# cnc_driver_3.net
KiCad netlist of a schematic drawn in EAGLE
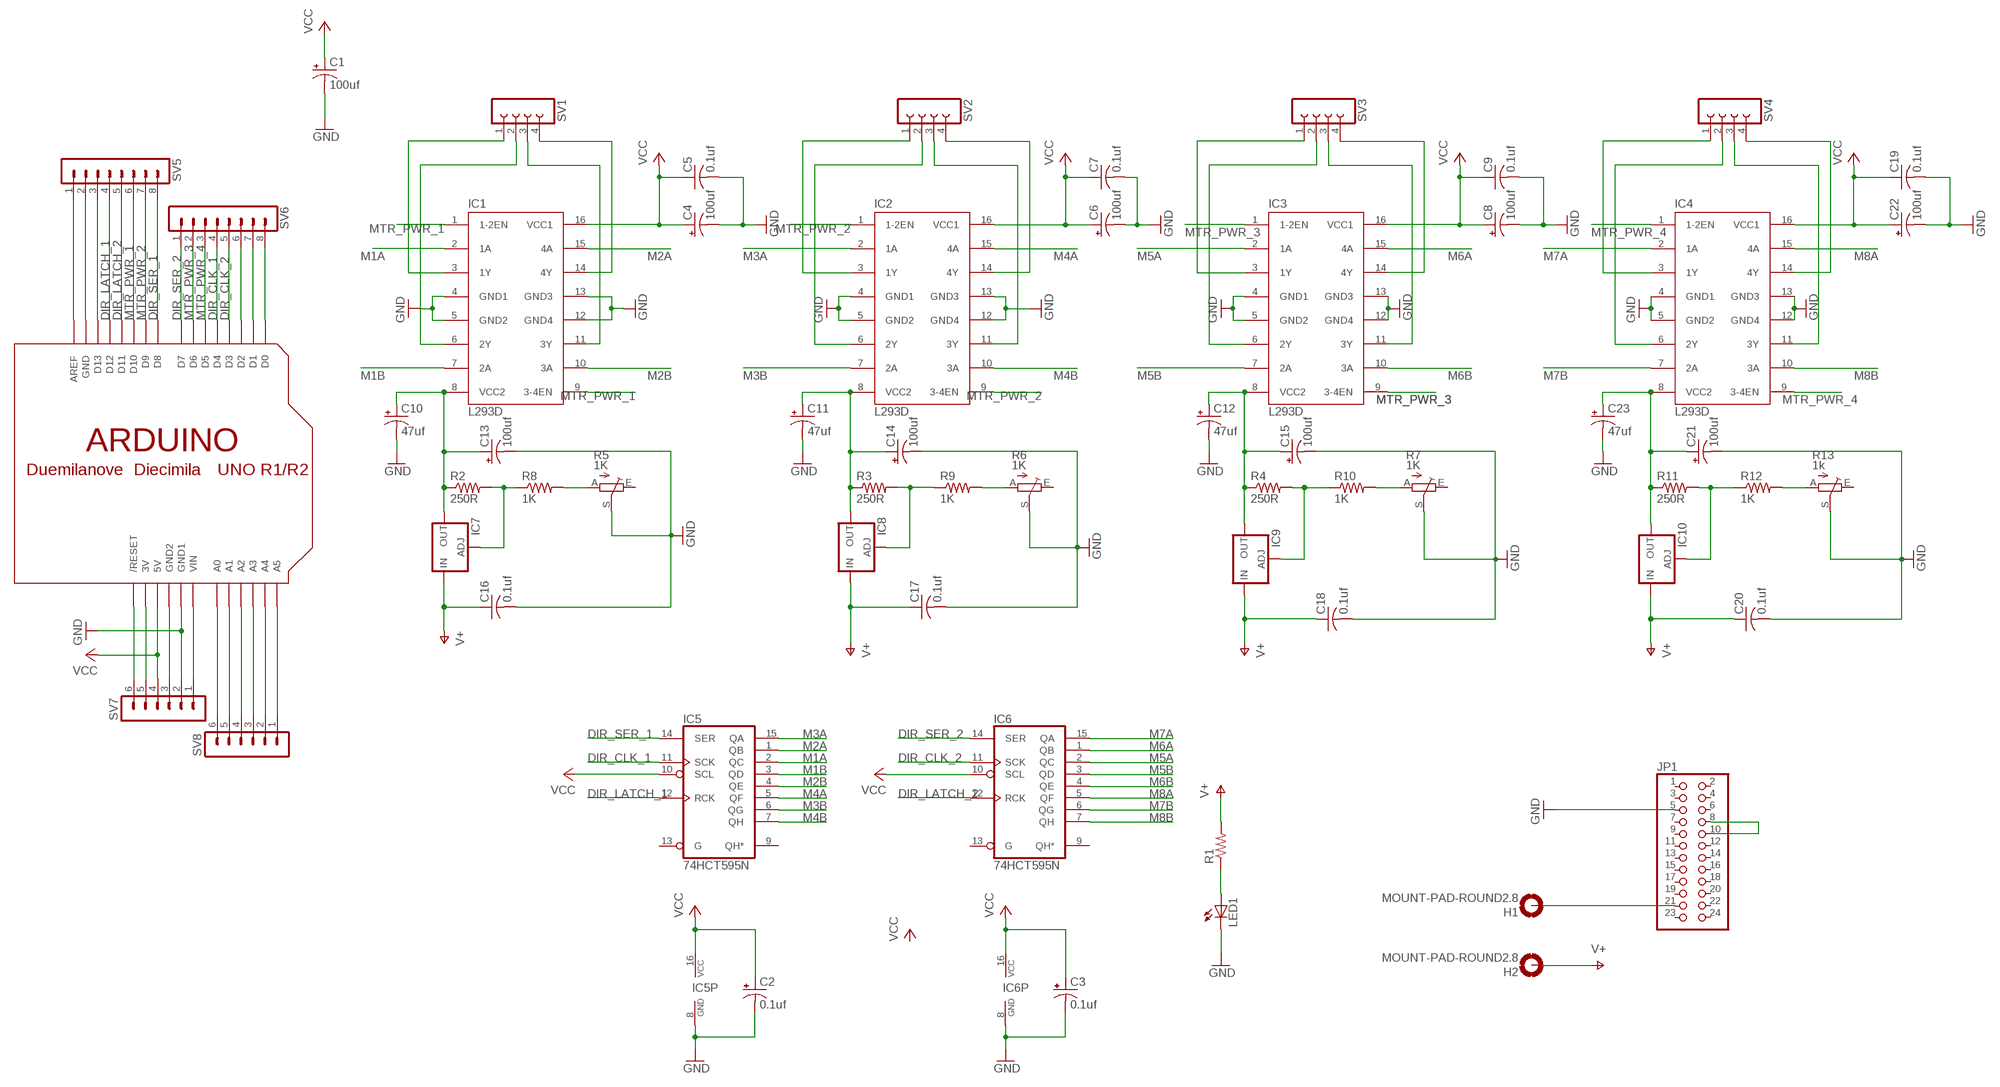
[diagram p0: schematic, sheet 1]

(export (version "E")
  (design (tool "Eeschema 10.0.6"))
  (components
    (comp (ref "C1")
      (value "100uf")
      (footprint "eagle-import:E2-5")
      (libsource (lib "eagle-import") (part "CPOL-USE2-5"))
    )
    (comp (ref "C2")
      (value "0.1uf")
      (footprint "eagle-import:E2-5")
      (libsource (lib "eagle-import") (part "CPOL-USE2-5"))
    )
    (comp (ref "C3")
      (value "0.1uf")
      (footprint "eagle-import:E2-5")
      (libsource (lib "eagle-import") (part "CPOL-USE2-5"))
    )
    (comp (ref "C4")
      (value "100uf")
      (footprint "eagle-import:E2-5")
      (libsource (lib "eagle-import") (part "CPOL-USE2-5"))
    )
    (comp (ref "C5")
      (value "0.1uf")
      (footprint "eagle-import:C025-025X050")
      (libsource (lib "eagle-import") (part "C-US025-025X050"))
    )
    (comp (ref "C6")
      (value "100uf")
      (footprint "eagle-import:E2-5")
      (libsource (lib "eagle-import") (part "CPOL-USE2-5"))
    )
    (comp (ref "C7")
      (value "0.1uf")
      (footprint "eagle-import:C025-025X050")
      (libsource (lib "eagle-import") (part "C-US025-025X050"))
    )
    (comp (ref "C8")
      (value "100uf")
      (footprint "eagle-import:E2-5")
      (libsource (lib "eagle-import") (part "CPOL-USE2-5"))
    )
    (comp (ref "C9")
      (value "0.1uf")
      (footprint "eagle-import:C025-025X050")
      (libsource (lib "eagle-import") (part "C-US025-025X050"))
    )
    (comp (ref "C10")
      (value "47uf")
      (footprint "eagle-import:E2-5")
      (libsource (lib "eagle-import") (part "CPOL-USE2-5"))
    )
    (comp (ref "C11")
      (value "47uf")
      (footprint "eagle-import:E2-5")
      (libsource (lib "eagle-import") (part "CPOL-USE2-5"))
    )
    (comp (ref "C12")
      (value "47uf")
      (footprint "eagle-import:E2-5")
      (libsource (lib "eagle-import") (part "CPOL-USE2-5"))
    )
    (comp (ref "C13")
      (value "100uf")
      (footprint "eagle-import:E3,5-8")
      (libsource (lib "eagle-import") (part "CPOL-USE3.5-8"))
    )
    (comp (ref "C14")
      (value "100uf")
      (footprint "eagle-import:E3,5-8")
      (libsource (lib "eagle-import") (part "CPOL-USE3.5-8"))
    )
    (comp (ref "C15")
      (value "100uf")
      (footprint "eagle-import:E3,5-8")
      (libsource (lib "eagle-import") (part "CPOL-USE3.5-8"))
    )
    (comp (ref "C16")
      (value "0.1uf")
      (footprint "eagle-import:C025-024X044")
      (libsource (lib "eagle-import") (part "C-US025-024X044"))
    )
    (comp (ref "C17")
      (value "0.1uf")
      (footprint "eagle-import:C025-024X044")
      (libsource (lib "eagle-import") (part "C-US025-024X044"))
    )
    (comp (ref "C18")
      (value "0.1uf")
      (footprint "eagle-import:C025-024X044")
      (libsource (lib "eagle-import") (part "C-US025-024X044"))
    )
    (comp (ref "C19")
      (value "0.1uf")
      (footprint "eagle-import:C025-025X050")
      (libsource (lib "eagle-import") (part "C-US025-025X050"))
    )
    (comp (ref "C20")
      (value "0.1uf")
      (footprint "eagle-import:C025-025X050")
      (libsource (lib "eagle-import") (part "C-US025-025X050"))
    )
    (comp (ref "C21")
      (value "100uf")
      (footprint "eagle-import:E3,5-8")
      (libsource (lib "eagle-import") (part "CPOL-USE3.5-8"))
    )
    (comp (ref "C22")
      (value "100uf")
      (footprint "eagle-import:E3,5-8")
      (libsource (lib "eagle-import") (part "CPOL-USE3.5-8"))
    )
    (comp (ref "C23")
      (value "47uf")
      (footprint "eagle-import:E3,5-8")
      (libsource (lib "eagle-import") (part "CPOL-USE3.5-8"))
    )
    (comp (ref "H1")
      (value "MOUNT-PAD-ROUND2.8")
      (footprint "eagle-import:2,8-PAD")
      (libsource (lib "eagle-import") (part "MOUNT-PAD-ROUND2.8"))
    )
    (comp (ref "H2")
      (value "MOUNT-PAD-ROUND2.8")
      (footprint "eagle-import:2,8-PAD")
      (libsource (lib "eagle-import") (part "MOUNT-PAD-ROUND2.8"))
    )
    (comp (ref "IC1")
      (value "L293D")
      (footprint "eagle-import:DIL16")
      (libsource (lib "eagle-import") (part "L293D"))
    )
    (comp (ref "IC2")
      (value "L293D")
      (footprint "eagle-import:DIL16")
      (libsource (lib "eagle-import") (part "L293D"))
    )
    (comp (ref "IC3")
      (value "L293D")
      (footprint "eagle-import:DIL16")
      (libsource (lib "eagle-import") (part "L293D"))
    )
    (comp (ref "IC4")
      (value "L293D")
      (footprint "eagle-import:DIL16")
      (libsource (lib "eagle-import") (part "L293D"))
    )
    (comp (ref "IC5")
      (value "74HCT595N")
      (footprint "eagle-import:DIL16")
      (libsource (lib "eagle-import") (part "74595NHCT"))
    )
    (comp (ref "IC6")
      (value "74HCT595N")
      (footprint "eagle-import:DIL16")
      (libsource (lib "eagle-import") (part "74595NHCT"))
    )
    (comp (ref "IC7")
      (value "LM317TS")
      (footprint "eagle-import:317TS")
      (libsource (lib "eagle-import") (part "LM317TS"))
    )
    (comp (ref "IC8")
      (value "LM317TS")
      (footprint "eagle-import:317TS")
      (libsource (lib "eagle-import") (part "LM317TS"))
    )
    (comp (ref "IC9")
      (value "LM317TS")
      (footprint "eagle-import:317TS")
      (libsource (lib "eagle-import") (part "LM317TS"))
    )
    (comp (ref "IC10")
      (value "LM317TS")
      (footprint "eagle-import:317TS")
      (libsource (lib "eagle-import") (part "LM317TS"))
    )
    (comp (ref "JP1")
      (value "PINHD-2X12")
      (footprint "eagle-import:2X12")
      (libsource (lib "eagle-import") (part "PINHD-2X12"))
    )
    (comp (ref "LED1")
      (value "LED5MM")
      (footprint "eagle-import:LED5MM")
      (libsource (lib "eagle-import") (part "LED5MM"))
    )
    (comp (ref "R1")
      (value "R-US_0204/7")
      (footprint "eagle-import:0204_7")
      (libsource (lib "eagle-import") (part "R-US_0204/7"))
    )
    (comp (ref "R2")
      (value "250R")
      (footprint "eagle-import:0207_7")
      (libsource (lib "eagle-import") (part "R-US_0207/7"))
    )
    (comp (ref "R3")
      (value "250R")
      (footprint "eagle-import:0207_7")
      (libsource (lib "eagle-import") (part "R-US_0207/7"))
    )
    (comp (ref "R4")
      (value "250R")
      (footprint "eagle-import:0207_7")
      (libsource (lib "eagle-import") (part "R-US_0207/7"))
    )
    (comp (ref "R5")
      (value "1K")
      (footprint "eagle-import:CA9H")
      (libsource (lib "eagle-import") (part "TRIM_EU-CA9H"))
    )
    (comp (ref "R6")
      (value "1K")
      (footprint "eagle-import:CA9H")
      (libsource (lib "eagle-import") (part "TRIM_EU-CA9H"))
    )
    (comp (ref "R7")
      (value "1K")
      (footprint "eagle-import:CA9H")
      (libsource (lib "eagle-import") (part "TRIM_EU-CA9H"))
    )
    (comp (ref "R8")
      (value "1K")
      (footprint "eagle-import:0207_7")
      (libsource (lib "eagle-import") (part "R-US_0207/7"))
    )
    (comp (ref "R9")
      (value "1K")
      (footprint "eagle-import:0207_7")
      (libsource (lib "eagle-import") (part "R-US_0207/7"))
    )
    (comp (ref "R10")
      (value "1K")
      (footprint "eagle-import:0207_7")
      (libsource (lib "eagle-import") (part "R-US_0207/7"))
    )
    (comp (ref "R11")
      (value "250R")
      (footprint "eagle-import:0207_7")
      (libsource (lib "eagle-import") (part "R-US_0207/7"))
    )
    (comp (ref "R12")
      (value "1K")
      (footprint "eagle-import:0207_7")
      (libsource (lib "eagle-import") (part "R-US_0207/7"))
    )
    (comp (ref "R13")
      (value "1k")
      (footprint "eagle-import:CA9H")
      (libsource (lib "eagle-import") (part "TRIM_EU-CA9H"))
    )
    (comp (ref "SV1")
      (value "FE04-1")
      (footprint "eagle-import:FE04-1")
      (libsource (lib "eagle-import") (part "FE04-1"))
    )
    (comp (ref "SV2")
      (value "FE04-1")
      (footprint "eagle-import:FE04-1")
      (libsource (lib "eagle-import") (part "FE04-1"))
    )
    (comp (ref "SV3")
      (value "FE04-1")
      (footprint "eagle-import:FE04-1")
      (libsource (lib "eagle-import") (part "FE04-1"))
    )
    (comp (ref "SV4")
      (value "FE04-1")
      (footprint "eagle-import:FE04-1")
      (libsource (lib "eagle-import") (part "FE04-1"))
    )
    (comp (ref "SV5")
      (value "MA08-1")
      (footprint "eagle-import:MA08-1")
      (libsource (lib "eagle-import") (part "MA08-1"))
    )
    (comp (ref "SV6")
      (value "MA08-1")
      (footprint "eagle-import:MA08-1")
      (libsource (lib "eagle-import") (part "MA08-1"))
    )
    (comp (ref "SV7")
      (value "MA06-1")
      (footprint "eagle-import:MA06-1")
      (libsource (lib "eagle-import") (part "MA06-1"))
    )
    (comp (ref "SV8")
      (value "MA06-1")
      (footprint "eagle-import:MA06-1")
      (libsource (lib "eagle-import") (part "MA06-1"))
    )
    (comp (ref "U$1")
      (value "ARDUINOUNO")
      (footprint "eagle-import:ARDUINO")
      (libsource (lib "eagle-import") (part "ARDUINOUNO"))
    )
  )
  (nets
    (net (code "1") (name "/DIR_CLK_1") (class "Default")
      (node (ref "IC5") (pin "11") (pinfunction "SCK_11") (pintype "input"))
      (node (ref "SV6") (pin "4") (pinfunction "4_4") (pintype "passive"))
      (node (ref "U$1") (pin "D4") (pinfunction "D4_D4") (pintype "bidirectional"))
    )
    (net (code "2") (name "/DIR_CLK_2") (class "Default")
      (node (ref "IC6") (pin "11") (pinfunction "SCK_11") (pintype "input"))
      (node (ref "SV6") (pin "5") (pinfunction "5_5") (pintype "passive"))
      (node (ref "U$1") (pin "D3") (pinfunction "D3_D3") (pintype "bidirectional"))
    )
    (net (code "3") (name "/DIR_LATCH_1") (class "Default")
      (node (ref "IC5") (pin "12") (pinfunction "RCK_12") (pintype "input"))
      (node (ref "SV5") (pin "4") (pinfunction "4_4") (pintype "passive"))
      (node (ref "U$1") (pin "D12") (pinfunction "D12_D12") (pintype "bidirectional"))
    )
    (net (code "4") (name "/DIR_LATCH_2") (class "Default")
      (node (ref "IC6") (pin "12") (pinfunction "RCK_12") (pintype "input"))
      (node (ref "SV5") (pin "5") (pinfunction "5_5") (pintype "passive"))
      (node (ref "U$1") (pin "D11") (pinfunction "D11_D11") (pintype "bidirectional"))
    )
    (net (code "5") (name "/DIR_SER_1") (class "Default")
      (node (ref "IC5") (pin "14") (pinfunction "SER_14") (pintype "input"))
      (node (ref "SV5") (pin "8") (pinfunction "8_8") (pintype "passive"))
      (node (ref "U$1") (pin "D8") (pinfunction "D8_D8") (pintype "bidirectional"))
    )
    (net (code "6") (name "/DIR_SER_2") (class "Default")
      (node (ref "IC6") (pin "14") (pinfunction "SER_14") (pintype "input"))
      (node (ref "SV6") (pin "1") (pinfunction "1_1") (pintype "passive"))
      (node (ref "U$1") (pin "D7") (pinfunction "D7_D7") (pintype "bidirectional"))
    )
    (net (code "7") (name "/M1A") (class "Default")
      (node (ref "IC1") (pin "2") (pinfunction "1A_2") (pintype "input"))
      (node (ref "IC5") (pin "2") (pinfunction "QC_2") (pintype "tri_state"))
    )
    (net (code "8") (name "/M1B") (class "Default")
      (node (ref "IC1") (pin "7") (pinfunction "2A_7") (pintype "input"))
      (node (ref "IC5") (pin "3") (pinfunction "QD_3") (pintype "tri_state"))
    )
    (net (code "9") (name "/M2A") (class "Default")
      (node (ref "IC1") (pin "15") (pinfunction "4A_15") (pintype "input"))
      (node (ref "IC5") (pin "1") (pinfunction "QB_1") (pintype "tri_state"))
    )
    (net (code "10") (name "/M2B") (class "Default")
      (node (ref "IC1") (pin "10") (pinfunction "3A_10") (pintype "input"))
      (node (ref "IC5") (pin "4") (pinfunction "QE_4") (pintype "tri_state"))
    )
    (net (code "11") (name "/M3A") (class "Default")
      (node (ref "IC2") (pin "2") (pinfunction "1A_2") (pintype "input"))
      (node (ref "IC5") (pin "15") (pinfunction "QA_15") (pintype "tri_state"))
    )
    (net (code "12") (name "/M3B") (class "Default")
      (node (ref "IC2") (pin "7") (pinfunction "2A_7") (pintype "input"))
      (node (ref "IC5") (pin "6") (pinfunction "QG_6") (pintype "tri_state"))
    )
    (net (code "13") (name "/M4A") (class "Default")
      (node (ref "IC2") (pin "15") (pinfunction "4A_15") (pintype "input"))
      (node (ref "IC5") (pin "5") (pinfunction "QF_5") (pintype "tri_state"))
    )
    (net (code "14") (name "/M4B") (class "Default")
      (node (ref "IC2") (pin "10") (pinfunction "3A_10") (pintype "input"))
      (node (ref "IC5") (pin "7") (pinfunction "QH_7") (pintype "tri_state"))
    )
    (net (code "15") (name "/M5A") (class "Default")
      (node (ref "IC3") (pin "2") (pinfunction "1A_2") (pintype "input"))
      (node (ref "IC6") (pin "2") (pinfunction "QC_2") (pintype "tri_state"))
    )
    (net (code "16") (name "/M5B") (class "Default")
      (node (ref "IC3") (pin "7") (pinfunction "2A_7") (pintype "input"))
      (node (ref "IC6") (pin "3") (pinfunction "QD_3") (pintype "tri_state"))
    )
    (net (code "17") (name "/M6A") (class "Default")
      (node (ref "IC3") (pin "15") (pinfunction "4A_15") (pintype "input"))
      (node (ref "IC6") (pin "1") (pinfunction "QB_1") (pintype "tri_state"))
    )
    (net (code "18") (name "/M6B") (class "Default")
      (node (ref "IC3") (pin "10") (pinfunction "3A_10") (pintype "input"))
      (node (ref "IC6") (pin "4") (pinfunction "QE_4") (pintype "tri_state"))
    )
    (net (code "19") (name "/M7A") (class "Default")
      (node (ref "IC4") (pin "2") (pinfunction "1A_2") (pintype "input"))
      (node (ref "IC6") (pin "15") (pinfunction "QA_15") (pintype "tri_state"))
    )
    (net (code "20") (name "/M7B") (class "Default")
      (node (ref "IC4") (pin "7") (pinfunction "2A_7") (pintype "input"))
      (node (ref "IC6") (pin "6") (pinfunction "QG_6") (pintype "tri_state"))
    )
    (net (code "21") (name "/M8A") (class "Default")
      (node (ref "IC4") (pin "15") (pinfunction "4A_15") (pintype "input"))
      (node (ref "IC6") (pin "5") (pinfunction "QF_5") (pintype "tri_state"))
    )
    (net (code "22") (name "/M8B") (class "Default")
      (node (ref "IC4") (pin "10") (pinfunction "3A_10") (pintype "input"))
      (node (ref "IC6") (pin "7") (pinfunction "QH_7") (pintype "tri_state"))
    )
    (net (code "23") (name "/MTR_PWR_1") (class "Default")
      (node (ref "IC1") (pin "1") (pinfunction "1-2EN_1") (pintype "input"))
      (node (ref "IC1") (pin "9") (pinfunction "3-4EN_9") (pintype "input"))
      (node (ref "SV5") (pin "6") (pinfunction "6_6") (pintype "passive"))
      (node (ref "U$1") (pin "D10") (pinfunction "D10_D10") (pintype "bidirectional"))
    )
    (net (code "24") (name "/MTR_PWR_2") (class "Default")
      (node (ref "IC2") (pin "1") (pinfunction "1-2EN_1") (pintype "input"))
      (node (ref "IC2") (pin "9") (pinfunction "3-4EN_9") (pintype "input"))
      (node (ref "SV5") (pin "7") (pinfunction "7_7") (pintype "passive"))
      (node (ref "U$1") (pin "D9") (pinfunction "D9_D9") (pintype "bidirectional"))
    )
    (net (code "25") (name "/MTR_PWR_3") (class "Default")
      (node (ref "IC3") (pin "1") (pinfunction "1-2EN_1") (pintype "input"))
      (node (ref "IC3") (pin "9") (pinfunction "3-4EN_9") (pintype "input"))
      (node (ref "SV6") (pin "2") (pinfunction "2_2") (pintype "passive"))
      (node (ref "U$1") (pin "D6") (pinfunction "D6_D6") (pintype "bidirectional"))
    )
    (net (code "26") (name "/MTR_PWR_4") (class "Default")
      (node (ref "IC4") (pin "1") (pinfunction "1-2EN_1") (pintype "input"))
      (node (ref "IC4") (pin "9") (pinfunction "3-4EN_9") (pintype "input"))
      (node (ref "SV6") (pin "3") (pinfunction "3_3") (pintype "passive"))
      (node (ref "U$1") (pin "D5") (pinfunction "D5_D5") (pintype "bidirectional"))
    )
    (net (code "27") (name "GND") (class "Default")
      (node (ref "C1") (pin "-") (pinfunction "-_-") (pintype "passive"))
      (node (ref "C10") (pin "-") (pinfunction "-_-") (pintype "passive"))
      (node (ref "C11") (pin "-") (pinfunction "-_-") (pintype "passive"))
      (node (ref "C12") (pin "-") (pinfunction "-_-") (pintype "passive"))
      (node (ref "C13") (pin "-") (pinfunction "-_-") (pintype "passive"))
      (node (ref "C14") (pin "-") (pinfunction "-_-") (pintype "passive"))
      (node (ref "C15") (pin "-") (pinfunction "-_-") (pintype "passive"))
      (node (ref "C16") (pin "2") (pinfunction "2_2") (pintype "passive"))
      (node (ref "C17") (pin "2") (pinfunction "2_2") (pintype "passive"))
      (node (ref "C18") (pin "2") (pinfunction "2_2") (pintype "passive"))
      (node (ref "C19") (pin "2") (pinfunction "2_2") (pintype "passive"))
      (node (ref "C2") (pin "-") (pinfunction "-_-") (pintype "passive"))
      (node (ref "C20") (pin "2") (pinfunction "2_2") (pintype "passive"))
      (node (ref "C21") (pin "-") (pinfunction "-_-") (pintype "passive"))
      (node (ref "C22") (pin "-") (pinfunction "-_-") (pintype "passive"))
      (node (ref "C23") (pin "-") (pinfunction "-_-") (pintype "passive"))
      (node (ref "C3") (pin "-") (pinfunction "-_-") (pintype "passive"))
      (node (ref "C4") (pin "-") (pinfunction "-_-") (pintype "passive"))
      (node (ref "C5") (pin "2") (pinfunction "2_2") (pintype "passive"))
      (node (ref "C6") (pin "-") (pinfunction "-_-") (pintype "passive"))
      (node (ref "C7") (pin "2") (pinfunction "2_2") (pintype "passive"))
      (node (ref "C8") (pin "-") (pinfunction "-_-") (pintype "passive"))
      (node (ref "C9") (pin "2") (pinfunction "2_2") (pintype "passive"))
      (node (ref "IC1") (pin "12") (pinfunction "GND4_12") (pintype "power_in"))
      (node (ref "IC1") (pin "13") (pinfunction "GND3_13") (pintype "power_in"))
      (node (ref "IC1") (pin "4") (pinfunction "GND1_4") (pintype "power_in"))
      (node (ref "IC1") (pin "5") (pinfunction "GND2_5") (pintype "power_in"))
      (node (ref "IC2") (pin "12") (pinfunction "GND4_12") (pintype "power_in"))
      (node (ref "IC2") (pin "13") (pinfunction "GND3_13") (pintype "power_in"))
      (node (ref "IC2") (pin "4") (pinfunction "GND1_4") (pintype "power_in"))
      (node (ref "IC2") (pin "5") (pinfunction "GND2_5") (pintype "power_in"))
      (node (ref "IC3") (pin "12") (pinfunction "GND4_12") (pintype "power_in"))
      (node (ref "IC3") (pin "13") (pinfunction "GND3_13") (pintype "power_in"))
      (node (ref "IC3") (pin "4") (pinfunction "GND1_4") (pintype "power_in"))
      (node (ref "IC3") (pin "5") (pinfunction "GND2_5") (pintype "power_in"))
      (node (ref "IC4") (pin "12") (pinfunction "GND4_12") (pintype "power_in"))
      (node (ref "IC4") (pin "13") (pinfunction "GND3_13") (pintype "power_in"))
      (node (ref "IC4") (pin "4") (pinfunction "GND1_4") (pintype "power_in"))
      (node (ref "IC4") (pin "5") (pinfunction "GND2_5") (pintype "power_in"))
      (node (ref "IC5") (pin "8") (pinfunction "GND_8") (pintype "power_in"))
      (node (ref "IC6") (pin "8") (pinfunction "GND_8") (pintype "power_in"))
      (node (ref "JP1") (pin "5") (pinfunction "5_5") (pintype "passive"))
      (node (ref "LED1") (pin "K") (pinfunction "C_K") (pintype "passive"))
      (node (ref "R13") (pin "S") (pinfunction "S_S") (pintype "passive"))
      (node (ref "R5") (pin "S") (pinfunction "S_S") (pintype "passive"))
      (node (ref "R6") (pin "S") (pinfunction "S_S") (pintype "passive"))
      (node (ref "R7") (pin "S") (pinfunction "S_S") (pintype "passive"))
      (node (ref "SV7") (pin "2") (pinfunction "2_2") (pintype "passive"))
      (node (ref "U$1") (pin "GND1") (pinfunction "GND1_GND1") (pintype "power_in"))
    )
    (net (code "28") (name "Net-(H1-MOUNT)") (class "Default")
      (node (ref "H1") (pin "B2,8") (pinfunction "MOUNT_B2,8") (pintype "passive"))
      (node (ref "JP1") (pin "21") (pinfunction "21_21") (pintype "passive"))
    )
    (net (code "29") (name "Net-(IC1-1Y)") (class "Default")
      (node (ref "IC1") (pin "3") (pinfunction "1Y_3") (pintype "output"))
      (node (ref "SV1") (pin "1") (pinfunction "1_1") (pintype "passive"))
    )
    (net (code "30") (name "Net-(IC1-2Y)") (class "Default")
      (node (ref "IC1") (pin "6") (pinfunction "2Y_6") (pintype "output"))
      (node (ref "SV1") (pin "2") (pinfunction "2_2") (pintype "passive"))
    )
    (net (code "31") (name "Net-(IC1-3Y)") (class "Default")
      (node (ref "IC1") (pin "11") (pinfunction "3Y_11") (pintype "output"))
      (node (ref "SV1") (pin "3") (pinfunction "3_3") (pintype "passive"))
    )
    (net (code "32") (name "Net-(IC1-4Y)") (class "Default")
      (node (ref "IC1") (pin "14") (pinfunction "4Y_14") (pintype "output"))
      (node (ref "SV1") (pin "4") (pinfunction "4_4") (pintype "passive"))
    )
    (net (code "33") (name "Net-(IC1-VCC2)") (class "Default")
      (node (ref "C10") (pin "+") (pinfunction "+_+") (pintype "passive"))
      (node (ref "C13") (pin "+") (pinfunction "+_+") (pintype "passive"))
      (node (ref "IC1") (pin "8") (pinfunction "VCC2_8") (pintype "power_in"))
      (node (ref "IC7") (pin "2") (pinfunction "OUT_2") (pintype "passive"))
      (node (ref "R2") (pin "1") (pinfunction "1_1") (pintype "passive"))
    )
    (net (code "34") (name "Net-(IC2-1Y)") (class "Default")
      (node (ref "IC2") (pin "3") (pinfunction "1Y_3") (pintype "output"))
      (node (ref "SV2") (pin "1") (pinfunction "1_1") (pintype "passive"))
    )
    (net (code "35") (name "Net-(IC2-2Y)") (class "Default")
      (node (ref "IC2") (pin "6") (pinfunction "2Y_6") (pintype "output"))
      (node (ref "SV2") (pin "2") (pinfunction "2_2") (pintype "passive"))
    )
    (net (code "36") (name "Net-(IC2-3Y)") (class "Default")
      (node (ref "IC2") (pin "11") (pinfunction "3Y_11") (pintype "output"))
      (node (ref "SV2") (pin "3") (pinfunction "3_3") (pintype "passive"))
    )
    (net (code "37") (name "Net-(IC2-4Y)") (class "Default")
      (node (ref "IC2") (pin "14") (pinfunction "4Y_14") (pintype "output"))
      (node (ref "SV2") (pin "4") (pinfunction "4_4") (pintype "passive"))
    )
    (net (code "38") (name "Net-(IC2-VCC2)") (class "Default")
      (node (ref "C11") (pin "+") (pinfunction "+_+") (pintype "passive"))
      (node (ref "C14") (pin "+") (pinfunction "+_+") (pintype "passive"))
      (node (ref "IC2") (pin "8") (pinfunction "VCC2_8") (pintype "power_in"))
      (node (ref "IC8") (pin "2") (pinfunction "OUT_2") (pintype "passive"))
      (node (ref "R3") (pin "1") (pinfunction "1_1") (pintype "passive"))
    )
    (net (code "39") (name "Net-(IC3-1Y)") (class "Default")
      (node (ref "IC3") (pin "3") (pinfunction "1Y_3") (pintype "output"))
      (node (ref "SV3") (pin "1") (pinfunction "1_1") (pintype "passive"))
    )
    (net (code "40") (name "Net-(IC3-2Y)") (class "Default")
      (node (ref "IC3") (pin "6") (pinfunction "2Y_6") (pintype "output"))
      (node (ref "SV3") (pin "2") (pinfunction "2_2") (pintype "passive"))
    )
    (net (code "41") (name "Net-(IC3-3Y)") (class "Default")
      (node (ref "IC3") (pin "11") (pinfunction "3Y_11") (pintype "output"))
      (node (ref "SV3") (pin "3") (pinfunction "3_3") (pintype "passive"))
    )
    (net (code "42") (name "Net-(IC3-4Y)") (class "Default")
      (node (ref "IC3") (pin "14") (pinfunction "4Y_14") (pintype "output"))
      (node (ref "SV3") (pin "4") (pinfunction "4_4") (pintype "passive"))
    )
    (net (code "43") (name "Net-(IC3-VCC2)") (class "Default")
      (node (ref "C12") (pin "+") (pinfunction "+_+") (pintype "passive"))
      (node (ref "C15") (pin "+") (pinfunction "+_+") (pintype "passive"))
      (node (ref "IC3") (pin "8") (pinfunction "VCC2_8") (pintype "power_in"))
      (node (ref "IC9") (pin "2") (pinfunction "OUT_2") (pintype "passive"))
      (node (ref "R4") (pin "1") (pinfunction "1_1") (pintype "passive"))
    )
    (net (code "44") (name "Net-(IC4-1Y)") (class "Default")
      (node (ref "IC4") (pin "3") (pinfunction "1Y_3") (pintype "output"))
      (node (ref "SV4") (pin "1") (pinfunction "1_1") (pintype "passive"))
    )
    (net (code "45") (name "Net-(IC4-2Y)") (class "Default")
      (node (ref "IC4") (pin "6") (pinfunction "2Y_6") (pintype "output"))
      (node (ref "SV4") (pin "2") (pinfunction "2_2") (pintype "passive"))
    )
    (net (code "46") (name "Net-(IC4-3Y)") (class "Default")
      (node (ref "IC4") (pin "11") (pinfunction "3Y_11") (pintype "output"))
      (node (ref "SV4") (pin "3") (pinfunction "3_3") (pintype "passive"))
    )
    (net (code "47") (name "Net-(IC4-4Y)") (class "Default")
      (node (ref "IC4") (pin "14") (pinfunction "4Y_14") (pintype "output"))
      (node (ref "SV4") (pin "4") (pinfunction "4_4") (pintype "passive"))
    )
    (net (code "48") (name "Net-(IC7-ADJ)") (class "Default")
      (node (ref "IC7") (pin "1") (pinfunction "ADJ_1") (pintype "input"))
      (node (ref "R2") (pin "2") (pinfunction "2_2") (pintype "passive"))
      (node (ref "R8") (pin "1") (pinfunction "1_1") (pintype "passive"))
    )
    (net (code "49") (name "Net-(IC8-ADJ)") (class "Default")
      (node (ref "IC8") (pin "1") (pinfunction "ADJ_1") (pintype "input"))
      (node (ref "R3") (pin "2") (pinfunction "2_2") (pintype "passive"))
      (node (ref "R9") (pin "1") (pinfunction "1_1") (pintype "passive"))
    )
    (net (code "50") (name "Net-(IC9-ADJ)") (class "Default")
      (node (ref "IC9") (pin "1") (pinfunction "ADJ_1") (pintype "input"))
      (node (ref "R10") (pin "1") (pinfunction "1_1") (pintype "passive"))
      (node (ref "R4") (pin "2") (pinfunction "2_2") (pintype "passive"))
    )
    (net (code "51") (name "Net-(IC10-ADJ)") (class "Default")
      (node (ref "IC10") (pin "1") (pinfunction "ADJ_1") (pintype "input"))
      (node (ref "R11") (pin "2") (pinfunction "2_2") (pintype "passive"))
      (node (ref "R12") (pin "1") (pinfunction "1_1") (pintype "passive"))
    )
    (net (code "52") (name "Net-(IC10-OUT)") (class "Default")
      (node (ref "C21") (pin "+") (pinfunction "+_+") (pintype "passive"))
      (node (ref "C23") (pin "+") (pinfunction "+_+") (pintype "passive"))
      (node (ref "IC10") (pin "2") (pinfunction "OUT_2") (pintype "passive"))
      (node (ref "IC4") (pin "8") (pinfunction "VCC2_8") (pintype "power_in"))
      (node (ref "R11") (pin "1") (pinfunction "1_1") (pintype "passive"))
    )
    (net (code "53") (name "Net-(JP1-Pad10)") (class "Default")
      (node (ref "JP1") (pin "10") (pinfunction "10_10") (pintype "passive"))
      (node (ref "JP1") (pin "8") (pinfunction "8_8") (pintype "passive"))
    )
    (net (code "54") (name "Net-(LED1-PadA)") (class "Default")
      (node (ref "LED1") (pin "A") (pinfunction "A_A") (pintype "passive"))
      (node (ref "R1") (pin "1") (pinfunction "1_1") (pintype "passive"))
    )
    (net (code "55") (name "Net-(R5-PadA)") (class "Default")
      (node (ref "R5") (pin "A") (pinfunction "A_A") (pintype "passive"))
      (node (ref "R8") (pin "2") (pinfunction "2_2") (pintype "passive"))
    )
    (net (code "56") (name "Net-(R6-PadA)") (class "Default")
      (node (ref "R6") (pin "A") (pinfunction "A_A") (pintype "passive"))
      (node (ref "R9") (pin "2") (pinfunction "2_2") (pintype "passive"))
    )
    (net (code "57") (name "Net-(R10-Pad2)") (class "Default")
      (node (ref "R10") (pin "2") (pinfunction "2_2") (pintype "passive"))
      (node (ref "R7") (pin "A") (pinfunction "A_A") (pintype "passive"))
    )
    (net (code "58") (name "Net-(R12-Pad2)") (class "Default")
      (node (ref "R12") (pin "2") (pinfunction "2_2") (pintype "passive"))
      (node (ref "R13") (pin "A") (pinfunction "A_A") (pintype "passive"))
    )
    (net (code "59") (name "Net-(SV5-Pad1)") (class "Default")
      (node (ref "SV5") (pin "1") (pinfunction "1_1") (pintype "passive"))
      (node (ref "U$1") (pin "AREF") (pinfunction "AREF_AREF") (pintype "bidirectional"))
    )
    (net (code "60") (name "Net-(SV5-Pad2)") (class "Default")
      (node (ref "SV5") (pin "2") (pinfunction "2_2") (pintype "passive"))
      (node (ref "U$1") (pin "GND") (pinfunction "GND_GND") (pintype "power_in"))
    )
    (net (code "61") (name "Net-(SV5-Pad3)") (class "Default")
      (node (ref "SV5") (pin "3") (pinfunction "3_3") (pintype "passive"))
      (node (ref "U$1") (pin "D13") (pinfunction "D13_D13") (pintype "bidirectional"))
    )
    (net (code "62") (name "Net-(SV6-Pad6)") (class "Default")
      (node (ref "SV6") (pin "6") (pinfunction "6_6") (pintype "passive"))
      (node (ref "U$1") (pin "D2") (pinfunction "D2_D2") (pintype "bidirectional"))
    )
    (net (code "63") (name "Net-(SV6-Pad7)") (class "Default")
      (node (ref "SV6") (pin "7") (pinfunction "7_7") (pintype "passive"))
      (node (ref "U$1") (pin "D1") (pinfunction "D1_D1") (pintype "bidirectional"))
    )
    (net (code "64") (name "Net-(SV6-Pad8)") (class "Default")
      (node (ref "SV6") (pin "8") (pinfunction "8_8") (pintype "passive"))
      (node (ref "U$1") (pin "D0") (pinfunction "D0_D0") (pintype "bidirectional"))
    )
    (net (code "65") (name "Net-(SV7-Pad1)") (class "Default")
      (node (ref "SV7") (pin "1") (pinfunction "1_1") (pintype "passive"))
      (node (ref "U$1") (pin "VIN") (pinfunction "VIN_VIN") (pintype "power_in"))
    )
    (net (code "66") (name "Net-(SV7-Pad3)") (class "Default")
      (node (ref "SV7") (pin "3") (pinfunction "3_3") (pintype "passive"))
      (node (ref "U$1") (pin "GND2") (pinfunction "GND2_GND2") (pintype "power_in"))
    )
    (net (code "67") (name "Net-(SV7-Pad5)") (class "Default")
      (node (ref "SV7") (pin "5") (pinfunction "5_5") (pintype "passive"))
      (node (ref "U$1") (pin "3V") (pinfunction "3V_3V") (pintype "power_in"))
    )
    (net (code "68") (name "Net-(SV8-Pad1)") (class "Default")
      (node (ref "SV8") (pin "1") (pinfunction "1_1") (pintype "passive"))
      (node (ref "U$1") (pin "A5") (pinfunction "A5_A5") (pintype "bidirectional"))
    )
    (net (code "69") (name "Net-(SV8-Pad2)") (class "Default")
      (node (ref "SV8") (pin "2") (pinfunction "2_2") (pintype "passive"))
      (node (ref "U$1") (pin "A4") (pinfunction "A4_A4") (pintype "bidirectional"))
    )
    (net (code "70") (name "Net-(SV8-Pad3)") (class "Default")
      (node (ref "SV8") (pin "3") (pinfunction "3_3") (pintype "passive"))
      (node (ref "U$1") (pin "A3") (pinfunction "A3_A3") (pintype "bidirectional"))
    )
    (net (code "71") (name "Net-(SV8-Pad4)") (class "Default")
      (node (ref "SV8") (pin "4") (pinfunction "4_4") (pintype "passive"))
      (node (ref "U$1") (pin "A2") (pinfunction "A2_A2") (pintype "bidirectional"))
    )
    (net (code "72") (name "Net-(SV8-Pad5)") (class "Default")
      (node (ref "SV8") (pin "5") (pinfunction "5_5") (pintype "passive"))
      (node (ref "U$1") (pin "A1") (pinfunction "A1_A1") (pintype "bidirectional"))
    )
    (net (code "73") (name "Net-(SV8-Pad6)") (class "Default")
      (node (ref "SV8") (pin "6") (pinfunction "6_6") (pintype "passive"))
      (node (ref "U$1") (pin "A0") (pinfunction "A0_A0") (pintype "bidirectional"))
    )
    (net (code "74") (name "Net-(U$1-{slash}RESET)") (class "Default")
      (node (ref "SV7") (pin "6") (pinfunction "6_6") (pintype "passive"))
      (node (ref "U$1") (pin "RESET") (pinfunction "/RESET_RESET") (pintype "bidirectional"))
    )
    (net (code "75") (name "V+") (class "Default")
      (node (ref "C16") (pin "1") (pinfunction "1_1") (pintype "passive"))
      (node (ref "C17") (pin "1") (pinfunction "1_1") (pintype "passive"))
      (node (ref "C18") (pin "1") (pinfunction "1_1") (pintype "passive"))
      (node (ref "C20") (pin "1") (pinfunction "1_1") (pintype "passive"))
      (node (ref "H2") (pin "B2,8") (pinfunction "MOUNT_B2,8") (pintype "passive"))
      (node (ref "IC10") (pin "3") (pinfunction "IN_3") (pintype "input"))
      (node (ref "IC7") (pin "3") (pinfunction "IN_3") (pintype "input"))
      (node (ref "IC8") (pin "3") (pinfunction "IN_3") (pintype "input"))
      (node (ref "IC9") (pin "3") (pinfunction "IN_3") (pintype "input"))
      (node (ref "R1") (pin "2") (pinfunction "2_2") (pintype "passive"))
    )
    (net (code "76") (name "VCC") (class "Default")
      (node (ref "C1") (pin "+") (pinfunction "+_+") (pintype "passive"))
      (node (ref "C19") (pin "1") (pinfunction "1_1") (pintype "passive"))
      (node (ref "C2") (pin "+") (pinfunction "+_+") (pintype "passive"))
      (node (ref "C22") (pin "+") (pinfunction "+_+") (pintype "passive"))
      (node (ref "C3") (pin "+") (pinfunction "+_+") (pintype "passive"))
      (node (ref "C4") (pin "+") (pinfunction "+_+") (pintype "passive"))
      (node (ref "C5") (pin "1") (pinfunction "1_1") (pintype "passive"))
      (node (ref "C6") (pin "+") (pinfunction "+_+") (pintype "passive"))
      (node (ref "C7") (pin "1") (pinfunction "1_1") (pintype "passive"))
      (node (ref "C8") (pin "+") (pinfunction "+_+") (pintype "passive"))
      (node (ref "C9") (pin "1") (pinfunction "1_1") (pintype "passive"))
      (node (ref "IC1") (pin "16") (pinfunction "VCC1_16") (pintype "power_in"))
      (node (ref "IC2") (pin "16") (pinfunction "VCC1_16") (pintype "power_in"))
      (node (ref "IC3") (pin "16") (pinfunction "VCC1_16") (pintype "power_in"))
      (node (ref "IC4") (pin "16") (pinfunction "VCC1_16") (pintype "power_in"))
      (node (ref "IC5") (pin "10") (pinfunction "SCL_10") (pintype "input"))
      (node (ref "IC5") (pin "16") (pinfunction "VCC_16") (pintype "power_in"))
      (node (ref "IC6") (pin "10") (pinfunction "SCL_10") (pintype "input"))
      (node (ref "IC6") (pin "16") (pinfunction "VCC_16") (pintype "power_in"))
      (node (ref "SV7") (pin "4") (pinfunction "4_4") (pintype "passive"))
      (node (ref "U$1") (pin "5V") (pinfunction "5V_5V") (pintype "power_in"))
    )
    (net (code "77") (name "unconnected-(IC5A-G-Pad13)") (class "Default")
      (node (ref "IC5") (pin "13") (pinfunction "G_13") (pintype "input"))
    )
    (net (code "78") (name "unconnected-(IC5A-QH*-Pad9)") (class "Default")
      (node (ref "IC5") (pin "9") (pinfunction "QH*_9") (pintype "tri_state"))
    )
    (net (code "79") (name "unconnected-(IC6A-G-Pad13)") (class "Default")
      (node (ref "IC6") (pin "13") (pinfunction "G_13") (pintype "input"))
    )
    (net (code "80") (name "unconnected-(IC6A-QH*-Pad9)") (class "Default")
      (node (ref "IC6") (pin "9") (pinfunction "QH*_9") (pintype "tri_state"))
    )
    (net (code "81") (name "unconnected-(JP1-Pad1)") (class "Default")
      (node (ref "JP1") (pin "1") (pinfunction "1_1") (pintype "passive"))
    )
    (net (code "82") (name "unconnected-(JP1-Pad2)") (class "Default")
      (node (ref "JP1") (pin "2") (pinfunction "2_2") (pintype "passive"))
    )
    (net (code "83") (name "unconnected-(JP1-Pad3)") (class "Default")
      (node (ref "JP1") (pin "3") (pinfunction "3_3") (pintype "passive"))
    )
    (net (code "84") (name "unconnected-(JP1-Pad4)") (class "Default")
      (node (ref "JP1") (pin "4") (pinfunction "4_4") (pintype "passive"))
    )
    (net (code "85") (name "unconnected-(JP1-Pad6)") (class "Default")
      (node (ref "JP1") (pin "6") (pinfunction "6_6") (pintype "passive"))
    )
    (net (code "86") (name "unconnected-(JP1-Pad7)") (class "Default")
      (node (ref "JP1") (pin "7") (pinfunction "7_7") (pintype "passive"))
    )
    (net (code "87") (name "unconnected-(JP1-Pad9)") (class "Default")
      (node (ref "JP1") (pin "9") (pinfunction "9_9") (pintype "passive"))
    )
    (net (code "88") (name "unconnected-(JP1-Pad11)") (class "Default")
      (node (ref "JP1") (pin "11") (pinfunction "11_11") (pintype "passive"))
    )
    (net (code "89") (name "unconnected-(JP1-Pad12)") (class "Default")
      (node (ref "JP1") (pin "12") (pinfunction "12_12") (pintype "passive"))
    )
    (net (code "90") (name "unconnected-(JP1-Pad13)") (class "Default")
      (node (ref "JP1") (pin "13") (pinfunction "13_13") (pintype "passive"))
    )
    (net (code "91") (name "unconnected-(JP1-Pad14)") (class "Default")
      (node (ref "JP1") (pin "14") (pinfunction "14_14") (pintype "passive"))
    )
    (net (code "92") (name "unconnected-(JP1-Pad15)") (class "Default")
      (node (ref "JP1") (pin "15") (pinfunction "15_15") (pintype "passive"))
    )
    (net (code "93") (name "unconnected-(JP1-Pad16)") (class "Default")
      (node (ref "JP1") (pin "16") (pinfunction "16_16") (pintype "passive"))
    )
    (net (code "94") (name "unconnected-(JP1-Pad17)") (class "Default")
      (node (ref "JP1") (pin "17") (pinfunction "17_17") (pintype "passive"))
    )
    (net (code "95") (name "unconnected-(JP1-Pad18)") (class "Default")
      (node (ref "JP1") (pin "18") (pinfunction "18_18") (pintype "passive"))
    )
    (net (code "96") (name "unconnected-(JP1-Pad19)") (class "Default")
      (node (ref "JP1") (pin "19") (pinfunction "19_19") (pintype "passive"))
    )
    (net (code "97") (name "unconnected-(JP1-Pad20)") (class "Default")
      (node (ref "JP1") (pin "20") (pinfunction "20_20") (pintype "passive"))
    )
    (net (code "98") (name "unconnected-(JP1-Pad22)") (class "Default")
      (node (ref "JP1") (pin "22") (pinfunction "22_22") (pintype "passive"))
    )
    (net (code "99") (name "unconnected-(JP1-Pad23)") (class "Default")
      (node (ref "JP1") (pin "23") (pinfunction "23_23") (pintype "passive"))
    )
    (net (code "100") (name "unconnected-(JP1-Pad24)") (class "Default")
      (node (ref "JP1") (pin "24") (pinfunction "24_24") (pintype "passive"))
    )
    (net (code "101") (name "unconnected-(R5-PadE)") (class "Default")
      (node (ref "R5") (pin "E") (pinfunction "E_E") (pintype "passive"))
    )
    (net (code "102") (name "unconnected-(R6-PadE)") (class "Default")
      (node (ref "R6") (pin "E") (pinfunction "E_E") (pintype "passive"))
    )
    (net (code "103") (name "unconnected-(R7-PadE)") (class "Default")
      (node (ref "R7") (pin "E") (pinfunction "E_E") (pintype "passive"))
    )
    (net (code "104") (name "unconnected-(R13-PadE)") (class "Default")
      (node (ref "R13") (pin "E") (pinfunction "E_E") (pintype "passive"))
    )
  )
)
